# Uni_Ali_001.net
KiCad netlist of a schematic drawn in EAGLE
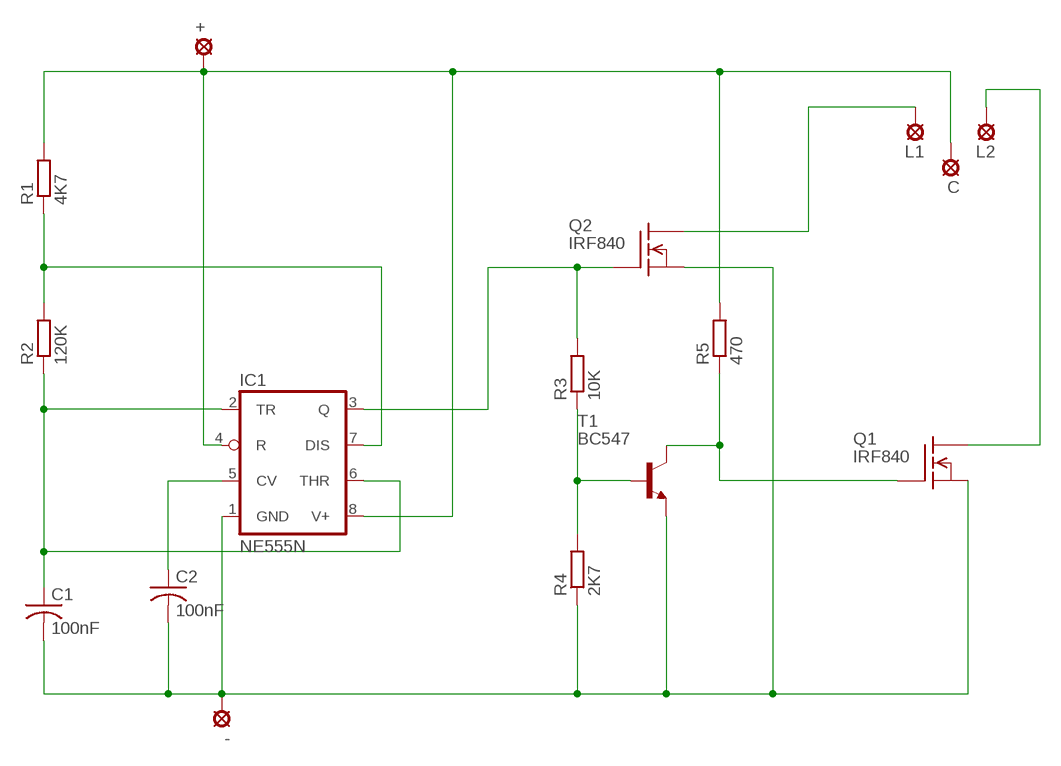
[diagram p0: schematic, sheet 1]

(export (version "E")
  (design (tool "Eeschema 10.0.6"))
  (components
    (comp (ref "+")
      (value "LSP10")
      (footprint "eagle-import:LSP10")
      (libsource (lib "eagle-import") (part "LSP10"))
    )
    (comp (ref "-")
      (value "LSP10")
      (footprint "eagle-import:LSP10")
      (libsource (lib "eagle-import") (part "LSP10"))
    )
    (comp (ref "C")
      (value "LSP10")
      (footprint "eagle-import:LSP10")
      (libsource (lib "eagle-import") (part "LSP10"))
    )
    (comp (ref "C1")
      (value "100nF")
      (footprint "eagle-import:C025-024X044")
      (libsource (lib "eagle-import") (part "C-US025-024X044"))
    )
    (comp (ref "C2")
      (value "100nF")
      (footprint "eagle-import:C025-024X044")
      (libsource (lib "eagle-import") (part "C-US025-024X044"))
    )
    (comp (ref "IC1")
      (value "NE555N")
      (footprint "eagle-import:DIL08")
      (libsource (lib "eagle-import") (part "555NNE"))
    )
    (comp (ref "L1")
      (value "LSP10")
      (footprint "eagle-import:LSP10")
      (libsource (lib "eagle-import") (part "LSP10"))
    )
    (comp (ref "L2")
      (value "LSP10")
      (footprint "eagle-import:LSP10")
      (libsource (lib "eagle-import") (part "LSP10"))
    )
    (comp (ref "Q1")
      (value "IRF840")
      (footprint "eagle-import:TO220")
      (libsource (lib "eagle-import") (part "IRF840"))
    )
    (comp (ref "Q2")
      (value "IRF840")
      (footprint "eagle-import:TO220")
      (libsource (lib "eagle-import") (part "IRF840"))
    )
    (comp (ref "R1")
      (value "4K7")
      (footprint "eagle-import:0204_7")
      (libsource (lib "eagle-import") (part "R-EU_0204/7"))
    )
    (comp (ref "R2")
      (value "120K")
      (footprint "eagle-import:0204_7")
      (libsource (lib "eagle-import") (part "R-EU_0204/7"))
    )
    (comp (ref "R3")
      (value "10K")
      (footprint "eagle-import:0204_7")
      (libsource (lib "eagle-import") (part "R-EU_0204/7"))
    )
    (comp (ref "R4")
      (value "2K7")
      (footprint "eagle-import:0204_7")
      (libsource (lib "eagle-import") (part "R-EU_0204/7"))
    )
    (comp (ref "R5")
      (value "470")
      (footprint "eagle-import:0204_7")
      (libsource (lib "eagle-import") (part "R-EU_0204/7"))
    )
    (comp (ref "T1")
      (value "BC547")
      (footprint "eagle-import:TO92")
      (libsource (lib "eagle-import") (part "BC547"))
    )
  )
  (nets
    (net (code "1") (name "Net-(IC1-CV)") (class "Default")
      (node (ref "C2") (pin "1") (pinfunction "1_1") (pintype "passive"))
      (node (ref "IC1") (pin "5") (pinfunction "CV_5") (pintype "input"))
    )
    (net (code "2") (name "Net-(IC1-DIS)") (class "Default")
      (node (ref "IC1") (pin "7") (pinfunction "DIS_7") (pintype "input"))
      (node (ref "R1") (pin "1") (pinfunction "1_1") (pintype "passive"))
      (node (ref "R2") (pin "2") (pinfunction "2_2") (pintype "passive"))
    )
    (net (code "3") (name "Net-(IC1-GND)") (class "Default")
      (node (ref "-") (pin "MP") (pinfunction "MP_MP") (pintype "passive"))
      (node (ref "C1") (pin "2") (pinfunction "2_2") (pintype "passive"))
      (node (ref "C2") (pin "2") (pinfunction "2_2") (pintype "passive"))
      (node (ref "IC1") (pin "1") (pinfunction "GND_1") (pintype "power_in"))
      (node (ref "Q1") (pin "3") (pinfunction "S_3") (pintype "passive"))
      (node (ref "Q2") (pin "3") (pinfunction "S_3") (pintype "passive"))
      (node (ref "R4") (pin "1") (pinfunction "1_1") (pintype "passive"))
      (node (ref "T1") (pin "1") (pinfunction "E_1") (pintype "passive"))
    )
    (net (code "4") (name "Net-(IC1-Q)") (class "Default")
      (node (ref "IC1") (pin "3") (pinfunction "Q_3") (pintype "output"))
      (node (ref "Q2") (pin "1") (pinfunction "G_1") (pintype "passive"))
      (node (ref "R3") (pin "2") (pinfunction "2_2") (pintype "passive"))
    )
    (net (code "5") (name "Net-(IC1-R)") (class "Default")
      (node (ref "+") (pin "MP") (pinfunction "MP_MP") (pintype "passive"))
      (node (ref "C") (pin "MP") (pinfunction "MP_MP") (pintype "passive"))
      (node (ref "IC1") (pin "4") (pinfunction "R_4") (pintype "input"))
      (node (ref "IC1") (pin "8") (pinfunction "V+_8") (pintype "power_in"))
      (node (ref "R1") (pin "2") (pinfunction "2_2") (pintype "passive"))
      (node (ref "R5") (pin "2") (pinfunction "2_2") (pintype "passive"))
    )
    (net (code "6") (name "Net-(IC1-THR)") (class "Default")
      (node (ref "C1") (pin "1") (pinfunction "1_1") (pintype "passive"))
      (node (ref "IC1") (pin "2") (pinfunction "TR_2") (pintype "input"))
      (node (ref "IC1") (pin "6") (pinfunction "THR_6") (pintype "input"))
      (node (ref "R2") (pin "1") (pinfunction "1_1") (pintype "passive"))
    )
    (net (code "7") (name "Net-(Q1-D)") (class "Default")
      (node (ref "L2") (pin "MP") (pinfunction "MP_MP") (pintype "passive"))
      (node (ref "Q1") (pin "2") (pinfunction "D_2") (pintype "passive"))
    )
    (net (code "8") (name "Net-(Q1-G)") (class "Default")
      (node (ref "Q1") (pin "1") (pinfunction "G_1") (pintype "passive"))
      (node (ref "R5") (pin "1") (pinfunction "1_1") (pintype "passive"))
      (node (ref "T1") (pin "3") (pinfunction "C_3") (pintype "passive"))
    )
    (net (code "9") (name "Net-(Q2-D)") (class "Default")
      (node (ref "L1") (pin "MP") (pinfunction "MP_MP") (pintype "passive"))
      (node (ref "Q2") (pin "2") (pinfunction "D_2") (pintype "passive"))
    )
    (net (code "10") (name "Net-(T1-B)") (class "Default")
      (node (ref "R3") (pin "1") (pinfunction "1_1") (pintype "passive"))
      (node (ref "R4") (pin "2") (pinfunction "2_2") (pintype "passive"))
      (node (ref "T1") (pin "2") (pinfunction "B_2") (pintype "passive"))
    )
  )
)
